# HC_Standoff.net
KiCad netlist of a schematic drawn in Altium Designer
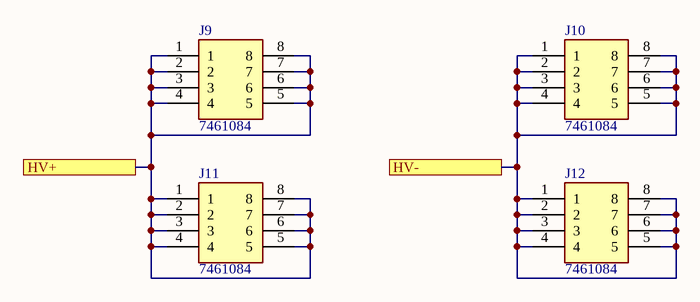
[diagram p0: HC Standoff.SchDoc]

(export (version "E")
  (design (tool "Eeschema 10.0.6"))
  (components
    (comp (ref "J9")
      (value "7461084")
      (footprint "PcbLib1:7461084")
      (description "Connector")
      (fields (field (name "MOUSER PART NUMBER") "710-7461084"))
      (libsource (lib "*") (part "7461084"))
    )
    (comp (ref "J10")
      (value "7461084")
      (footprint "PcbLib1:7461084")
      (description "Connector")
      (fields (field (name "MOUSER PART NUMBER") "710-7461084"))
      (libsource (lib "*") (part "7461084"))
    )
    (comp (ref "J11")
      (value "7461084")
      (footprint "PcbLib1:7461084")
      (description "Connector")
      (fields (field (name "MOUSER PART NUMBER") "710-7461084"))
      (libsource (lib "*") (part "7461084"))
    )
    (comp (ref "J12")
      (value "7461084")
      (footprint "PcbLib1:7461084")
      (description "Connector")
      (fields (field (name "MOUSER PART NUMBER") "710-7461084"))
      (libsource (lib "*") (part "7461084"))
    )
  )
  (nets
    (net (code "1") (name "/HV+") (class "Default")
      (node (ref "J11") (pin "1") (pinfunction "1_1") (pintype "passive"))
      (node (ref "J11") (pin "2") (pinfunction "2_2") (pintype "passive"))
      (node (ref "J11") (pin "3") (pinfunction "3_3") (pintype "passive"))
      (node (ref "J11") (pin "4") (pinfunction "4_4") (pintype "passive"))
      (node (ref "J11") (pin "5") (pinfunction "5_5") (pintype "passive"))
      (node (ref "J11") (pin "6") (pinfunction "6_6") (pintype "passive"))
      (node (ref "J11") (pin "7") (pinfunction "7_7") (pintype "passive"))
      (node (ref "J11") (pin "8") (pinfunction "8_8") (pintype "passive"))
      (node (ref "J9") (pin "1") (pinfunction "1_1") (pintype "passive"))
      (node (ref "J9") (pin "2") (pinfunction "2_2") (pintype "passive"))
      (node (ref "J9") (pin "3") (pinfunction "3_3") (pintype "passive"))
      (node (ref "J9") (pin "4") (pinfunction "4_4") (pintype "passive"))
      (node (ref "J9") (pin "5") (pinfunction "5_5") (pintype "passive"))
      (node (ref "J9") (pin "6") (pinfunction "6_6") (pintype "passive"))
      (node (ref "J9") (pin "7") (pinfunction "7_7") (pintype "passive"))
      (node (ref "J9") (pin "8") (pinfunction "8_8") (pintype "passive"))
    )
    (net (code "2") (name "/HV-") (class "Default")
      (node (ref "J10") (pin "1") (pinfunction "1_1") (pintype "passive"))
      (node (ref "J10") (pin "2") (pinfunction "2_2") (pintype "passive"))
      (node (ref "J10") (pin "3") (pinfunction "3_3") (pintype "passive"))
      (node (ref "J10") (pin "4") (pinfunction "4_4") (pintype "passive"))
      (node (ref "J10") (pin "5") (pinfunction "5_5") (pintype "passive"))
      (node (ref "J10") (pin "6") (pinfunction "6_6") (pintype "passive"))
      (node (ref "J10") (pin "7") (pinfunction "7_7") (pintype "passive"))
      (node (ref "J10") (pin "8") (pinfunction "8_8") (pintype "passive"))
      (node (ref "J12") (pin "1") (pinfunction "1_1") (pintype "passive"))
      (node (ref "J12") (pin "2") (pinfunction "2_2") (pintype "passive"))
      (node (ref "J12") (pin "3") (pinfunction "3_3") (pintype "passive"))
      (node (ref "J12") (pin "4") (pinfunction "4_4") (pintype "passive"))
      (node (ref "J12") (pin "5") (pinfunction "5_5") (pintype "passive"))
      (node (ref "J12") (pin "6") (pinfunction "6_6") (pintype "passive"))
      (node (ref "J12") (pin "7") (pinfunction "7_7") (pintype "passive"))
      (node (ref "J12") (pin "8") (pinfunction "8_8") (pintype "passive"))
    )
  )
)
